# Smart_Environment_Schematic.net
KiCad netlist of a schematic drawn in EasyEDA
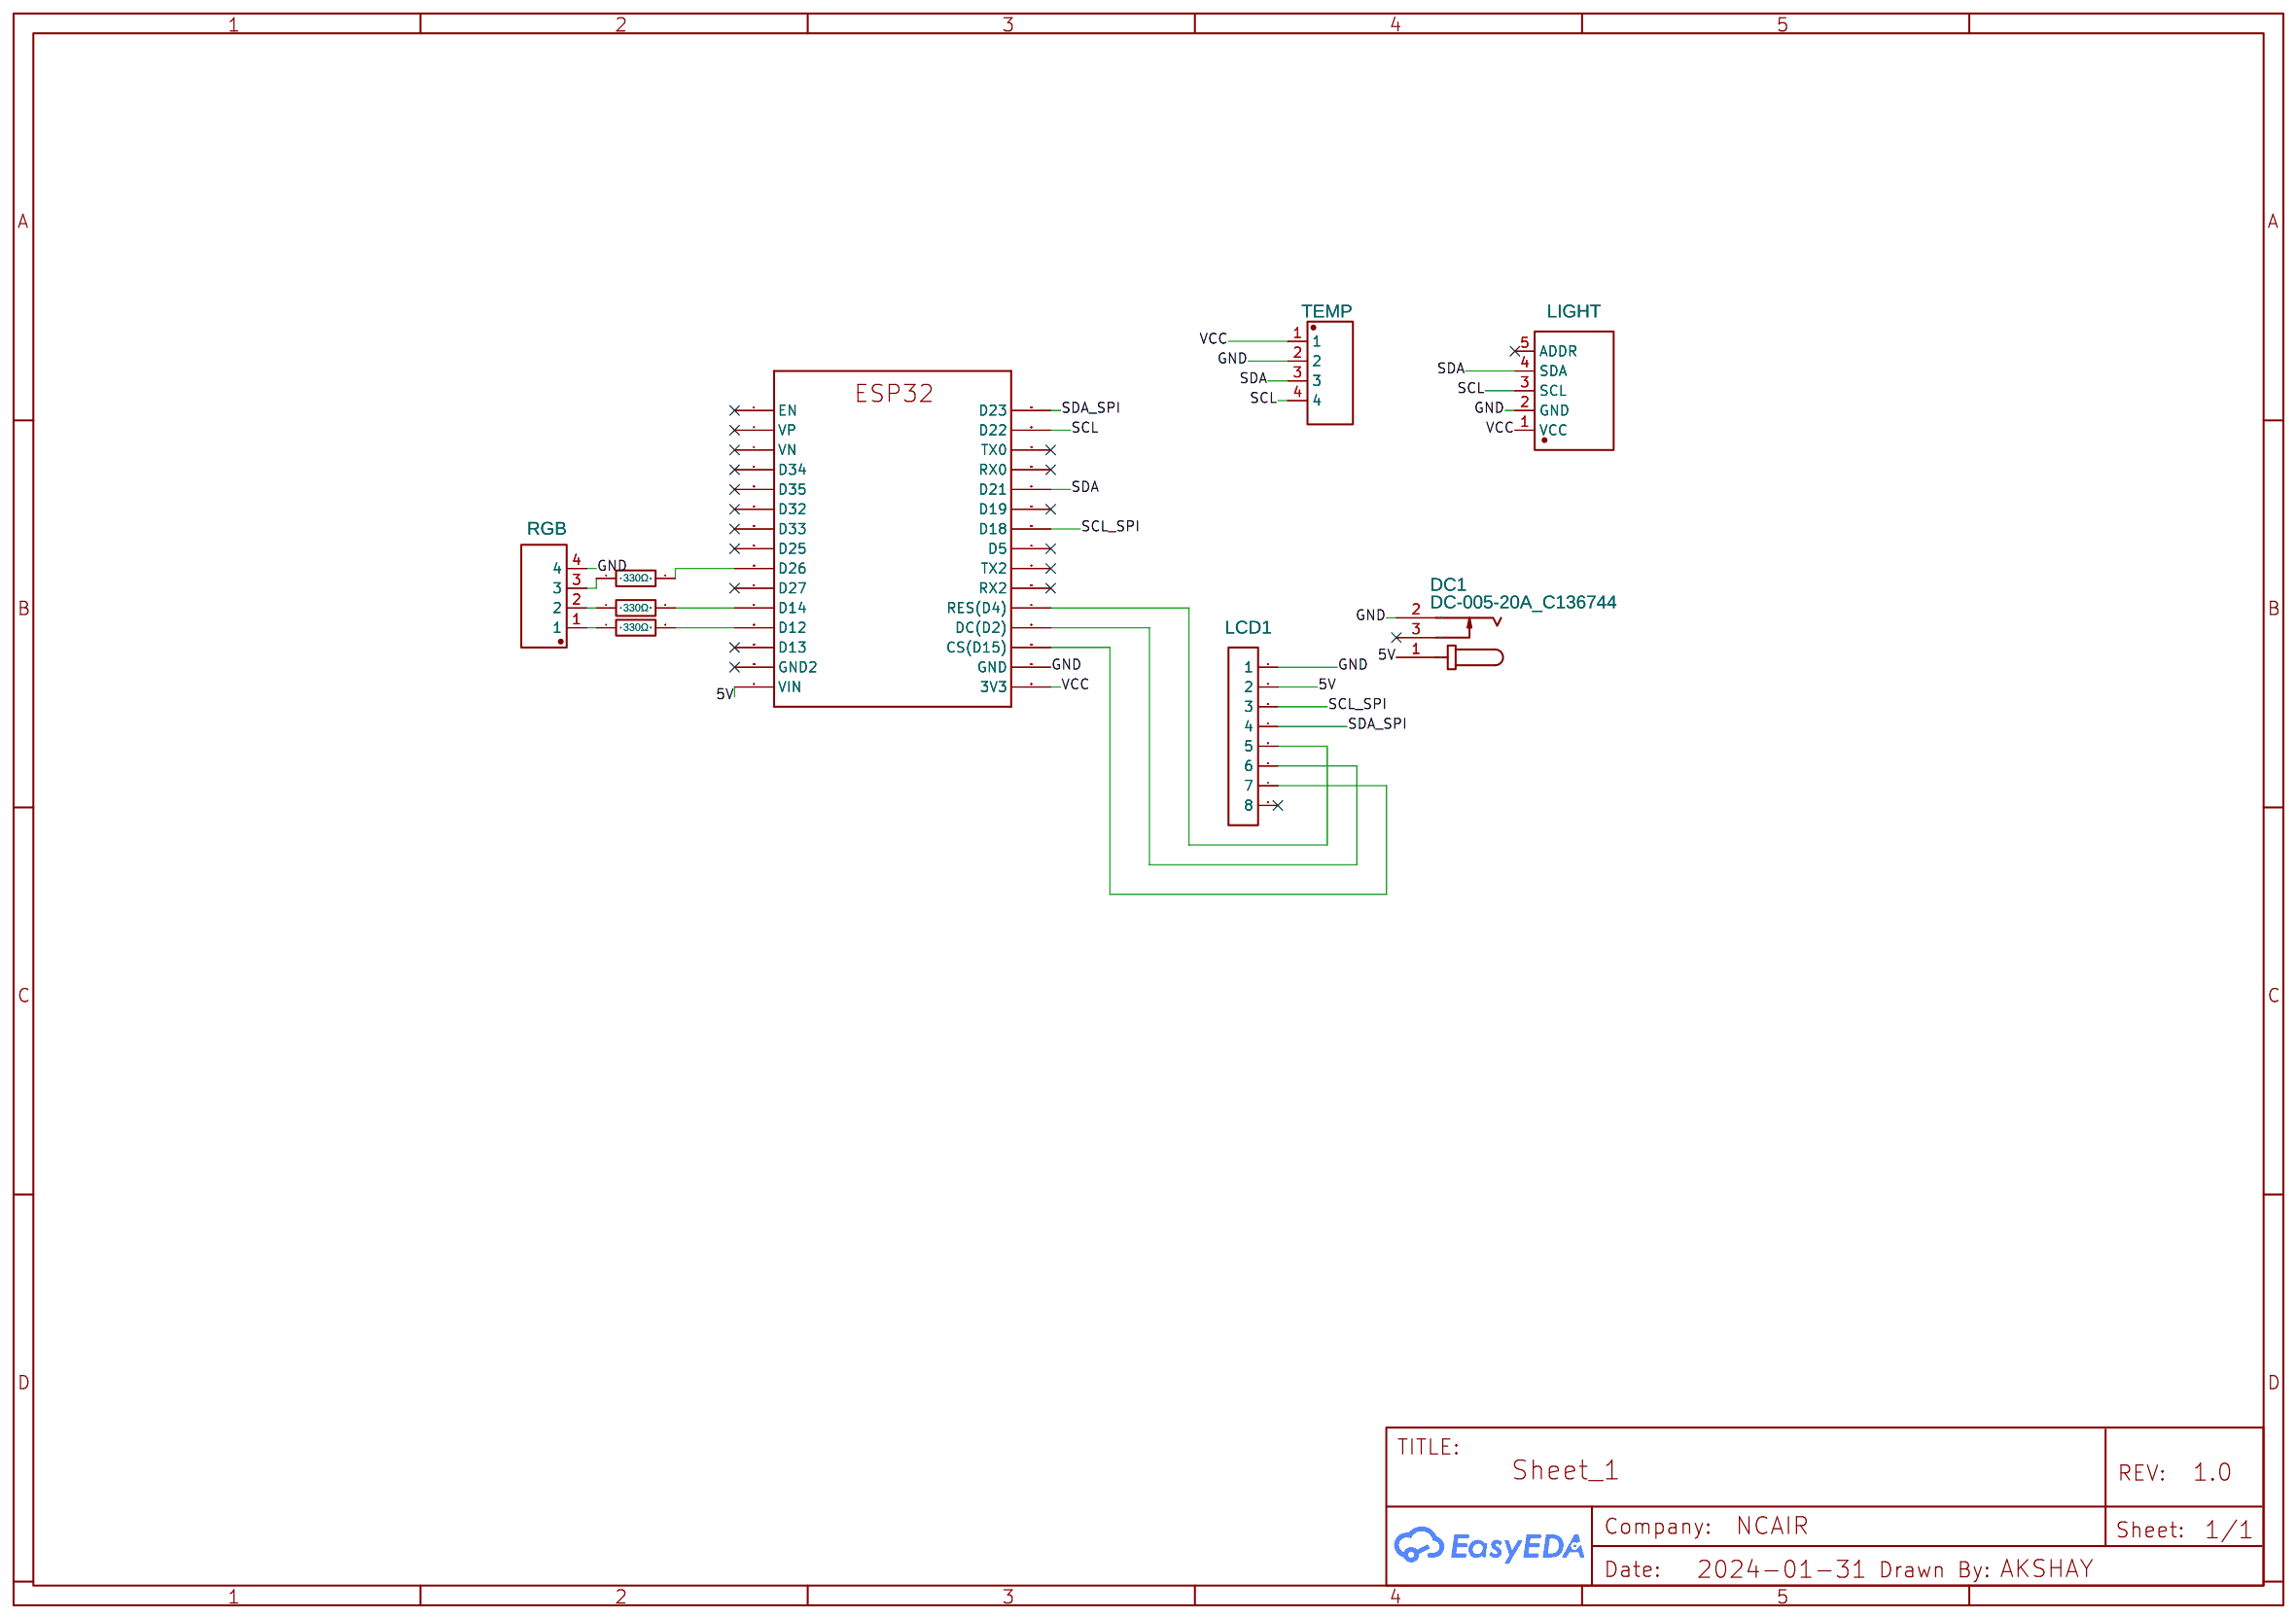
[diagram p0: schematic sheet]

(export (version "E")
  (design (tool "Eeschema 10.0.6"))
  (components
    (comp (ref "1") (value "ESP32") (libsource (lib "") (part "ESP32-DEVKIT-V1-30PIN")))
    (comp (ref "DC1")
      (value "DC-005-20A_C136744")
      (fields (field (name "Manufacturer Part") "DC-005-20A") (field (name "Manufacturer") "韩国韩荣"))
      (libsource (lib "") (part "DC-005-20A_C136744"))
    )
    (comp (ref "LCD1") (value "PINHEADER-8PIN") (libsource (lib "") (part "PINHEADER-8PIN")))
    (comp (ref "LIGHT") (value "IR") (libsource (lib "") (part "My_BH1750")))
    (comp (ref "R1")
      (value "330Ω")
      (fields (field (name "Manufacturer Part") "MFR0W4F3300A50") (field (name "Manufacturer") "UniOhm"))
      (libsource (lib "") (part "330 ohm resistor"))
    )
    (comp (ref "R2")
      (value "330Ω")
      (fields (field (name "Manufacturer Part") "MFR0W4F3300A50") (field (name "Manufacturer") "UniOhm"))
      (libsource (lib "") (part "330 ohm resistor"))
    )
    (comp (ref "R3")
      (value "330Ω")
      (fields (field (name "Manufacturer Part") "MFR0W4F3300A50") (field (name "Manufacturer") "UniOhm"))
      (libsource (lib "") (part "330 ohm resistor"))
    )
    (comp (ref "RGB1") (value "RGB") (libsource (lib "") (part "HEADER-2.54_1X4_1")))
    (comp (ref "SHT3X") (value "TEMP") (libsource (lib "") (part "HEADER-2.54_1X4")))
  )
  (nets
    (net (code "1") (name "/5V") (class "Default")
      (node (ref "1") (pin "VIN") (pinfunction "VIN_VIN") (pintype "unspecified"))
      (node (ref "DC1") (pin "1") (pinfunction "1_1") (pintype "unspecified"))
      (node (ref "LCD1") (pin "2") (pinfunction "2_2") (pintype "input"))
    )
    (net (code "2") (name "/GND") (class "Default")
      (node (ref "1") (pin "GND") (pinfunction "GND_GND") (pintype "unspecified"))
      (node (ref "DC1") (pin "2") (pinfunction "2_2") (pintype "unspecified"))
      (node (ref "LCD1") (pin "1") (pinfunction "1_1") (pintype "input"))
      (node (ref "LIGHT") (pin "2") (pinfunction "GND_2") (pintype "unspecified"))
      (node (ref "RGB1") (pin "4") (pinfunction "4_4") (pintype "unspecified"))
      (node (ref "SHT3X") (pin "2") (pinfunction "2_2") (pintype "unspecified"))
    )
    (net (code "3") (name "/SCL") (class "Default")
      (node (ref "1") (pin "D22") (pinfunction "D22_D22") (pintype "unspecified"))
      (node (ref "LIGHT") (pin "3") (pinfunction "SCL_3") (pintype "unspecified"))
      (node (ref "SHT3X") (pin "4") (pinfunction "4_4") (pintype "unspecified"))
    )
    (net (code "4") (name "/SCL_SPI") (class "Default")
      (node (ref "1") (pin "D18") (pinfunction "D18_D18") (pintype "unspecified"))
      (node (ref "LCD1") (pin "3") (pinfunction "3_3") (pintype "input"))
    )
    (net (code "5") (name "/SDA") (class "Default")
      (node (ref "1") (pin "D21") (pinfunction "D21_D21") (pintype "unspecified"))
      (node (ref "LIGHT") (pin "4") (pinfunction "SDA_4") (pintype "unspecified"))
      (node (ref "SHT3X") (pin "3") (pinfunction "3_3") (pintype "unspecified"))
    )
    (net (code "6") (name "/SDA_SPI") (class "Default")
      (node (ref "1") (pin "D23") (pinfunction "D23_D23") (pintype "unspecified"))
      (node (ref "LCD1") (pin "4") (pinfunction "4_4") (pintype "input"))
    )
    (net (code "7") (name "/VCC") (class "Default")
      (node (ref "1") (pin "3V3") (pinfunction "3V3_3V3") (pintype "unspecified"))
      (node (ref "LIGHT") (pin "1") (pinfunction "VCC_1") (pintype "unspecified"))
      (node (ref "SHT3X") (pin "1") (pinfunction "1_1") (pintype "unspecified"))
    )
    (net (code "8") (name "Net-(1-CS(D15))") (class "Default")
      (node (ref "1") (pin "D15") (pinfunction "CS(D15)_D15") (pintype "unspecified"))
      (node (ref "LCD1") (pin "7") (pinfunction "7_7") (pintype "input"))
    )
    (net (code "9") (name "Net-(1-DC(D2))") (class "Default")
      (node (ref "1") (pin "D2") (pinfunction "DC(D2)_D2") (pintype "unspecified"))
      (node (ref "LCD1") (pin "6") (pinfunction "6_6") (pintype "input"))
    )
    (net (code "10") (name "Net-(1-PadD12)") (class "Default")
      (node (ref "1") (pin "D12") (pinfunction "D12_D12") (pintype "unspecified"))
      (node (ref "R3") (pin "2") (pinfunction "2_2") (pintype "input"))
    )
    (net (code "11") (name "Net-(1-PadD14)") (class "Default")
      (node (ref "1") (pin "D14") (pinfunction "D14_D14") (pintype "unspecified"))
      (node (ref "R2") (pin "2") (pinfunction "2_2") (pintype "input"))
    )
    (net (code "12") (name "Net-(1-PadD26)") (class "Default")
      (node (ref "1") (pin "D26") (pinfunction "D26_D26") (pintype "unspecified"))
      (node (ref "R1") (pin "2") (pinfunction "2_2") (pintype "input"))
    )
    (net (code "13") (name "Net-(1-RES(D4))") (class "Default")
      (node (ref "1") (pin "D4") (pinfunction "RES(D4)_D4") (pintype "unspecified"))
      (node (ref "LCD1") (pin "5") (pinfunction "5_5") (pintype "input"))
    )
    (net (code "14") (name "Net-(R1-Pad1)") (class "Default")
      (node (ref "R1") (pin "1") (pinfunction "1_1") (pintype "input"))
      (node (ref "RGB1") (pin "3") (pinfunction "3_3") (pintype "unspecified"))
    )
    (net (code "15") (name "Net-(R2-Pad1)") (class "Default")
      (node (ref "R2") (pin "1") (pinfunction "1_1") (pintype "input"))
      (node (ref "RGB1") (pin "2") (pinfunction "2_2") (pintype "unspecified"))
    )
    (net (code "16") (name "Net-(R3-Pad1)") (class "Default")
      (node (ref "R3") (pin "1") (pinfunction "1_1") (pintype "input"))
      (node (ref "RGB1") (pin "1") (pinfunction "1_1") (pintype "unspecified"))
    )
    (net (code "17") (name "unconnected-(1-PadD5)") (class "Default")
      (node (ref "1") (pin "D5") (pinfunction "D5_D5") (pintype "unspecified+no_connect"))
    )
    (net (code "18") (name "unconnected-(1-PadD13)") (class "Default")
      (node (ref "1") (pin "D13") (pinfunction "D13_D13") (pintype "unspecified+no_connect"))
    )
    (net (code "19") (name "unconnected-(1-PadD19)") (class "Default")
      (node (ref "1") (pin "D19") (pinfunction "D19_D19") (pintype "unspecified+no_connect"))
    )
    (net (code "20") (name "unconnected-(1-PadD25)") (class "Default")
      (node (ref "1") (pin "D25") (pinfunction "D25_D25") (pintype "unspecified+no_connect"))
    )
    (net (code "21") (name "unconnected-(1-PadD27)") (class "Default")
      (node (ref "1") (pin "D27") (pinfunction "D27_D27") (pintype "unspecified+no_connect"))
    )
    (net (code "22") (name "unconnected-(1-PadD32)") (class "Default")
      (node (ref "1") (pin "D32") (pinfunction "D32_D32") (pintype "unspecified+no_connect"))
    )
    (net (code "23") (name "unconnected-(1-PadD33)") (class "Default")
      (node (ref "1") (pin "D33") (pinfunction "D33_D33") (pintype "unspecified+no_connect"))
    )
    (net (code "24") (name "unconnected-(1-PadD34)") (class "Default")
      (node (ref "1") (pin "D34") (pinfunction "D34_D34") (pintype "unspecified+no_connect"))
    )
    (net (code "25") (name "unconnected-(1-PadD35)") (class "Default")
      (node (ref "1") (pin "D35") (pinfunction "D35_D35") (pintype "unspecified+no_connect"))
    )
    (net (code "26") (name "unconnected-(1-PadEN)") (class "Default")
      (node (ref "1") (pin "EN") (pinfunction "EN_EN") (pintype "unspecified+no_connect"))
    )
    (net (code "27") (name "unconnected-(1-PadGND2)") (class "Default")
      (node (ref "1") (pin "GND2") (pinfunction "GND2_GND2") (pintype "unspecified+no_connect"))
    )
    (net (code "28") (name "unconnected-(1-PadRX0)") (class "Default")
      (node (ref "1") (pin "RX0") (pinfunction "RX0_RX0") (pintype "unspecified+no_connect"))
    )
    (net (code "29") (name "unconnected-(1-PadRX2)") (class "Default")
      (node (ref "1") (pin "RX2") (pinfunction "RX2_RX2") (pintype "unspecified+no_connect"))
    )
    (net (code "30") (name "unconnected-(1-PadTX0)") (class "Default")
      (node (ref "1") (pin "TX0") (pinfunction "TX0_TX0") (pintype "unspecified+no_connect"))
    )
    (net (code "31") (name "unconnected-(1-PadTX2)") (class "Default")
      (node (ref "1") (pin "TX2") (pinfunction "TX2_TX2") (pintype "unspecified+no_connect"))
    )
    (net (code "32") (name "unconnected-(1-PadVN)") (class "Default")
      (node (ref "1") (pin "VN") (pinfunction "VN_VN") (pintype "unspecified+no_connect"))
    )
    (net (code "33") (name "unconnected-(1-PadVP)") (class "Default")
      (node (ref "1") (pin "VP") (pinfunction "VP_VP") (pintype "unspecified+no_connect"))
    )
    (net (code "34") (name "unconnected-(DC1-Pad3)") (class "Default")
      (node (ref "DC1") (pin "3") (pinfunction "3_3") (pintype "unspecified+no_connect"))
    )
    (net (code "35") (name "unconnected-(LCD1-Pad8)") (class "Default")
      (node (ref "LCD1") (pin "8") (pinfunction "8_8") (pintype "input+no_connect"))
    )
    (net (code "36") (name "unconnected-(LIGHT-ADDR-Pad5)") (class "Default")
      (node (ref "LIGHT") (pin "5") (pinfunction "ADDR_5") (pintype "unspecified+no_connect"))
    )
  )
)
